# Urukul_FPGA_Config.net
KiCad netlist of a schematic drawn in Altium Designer
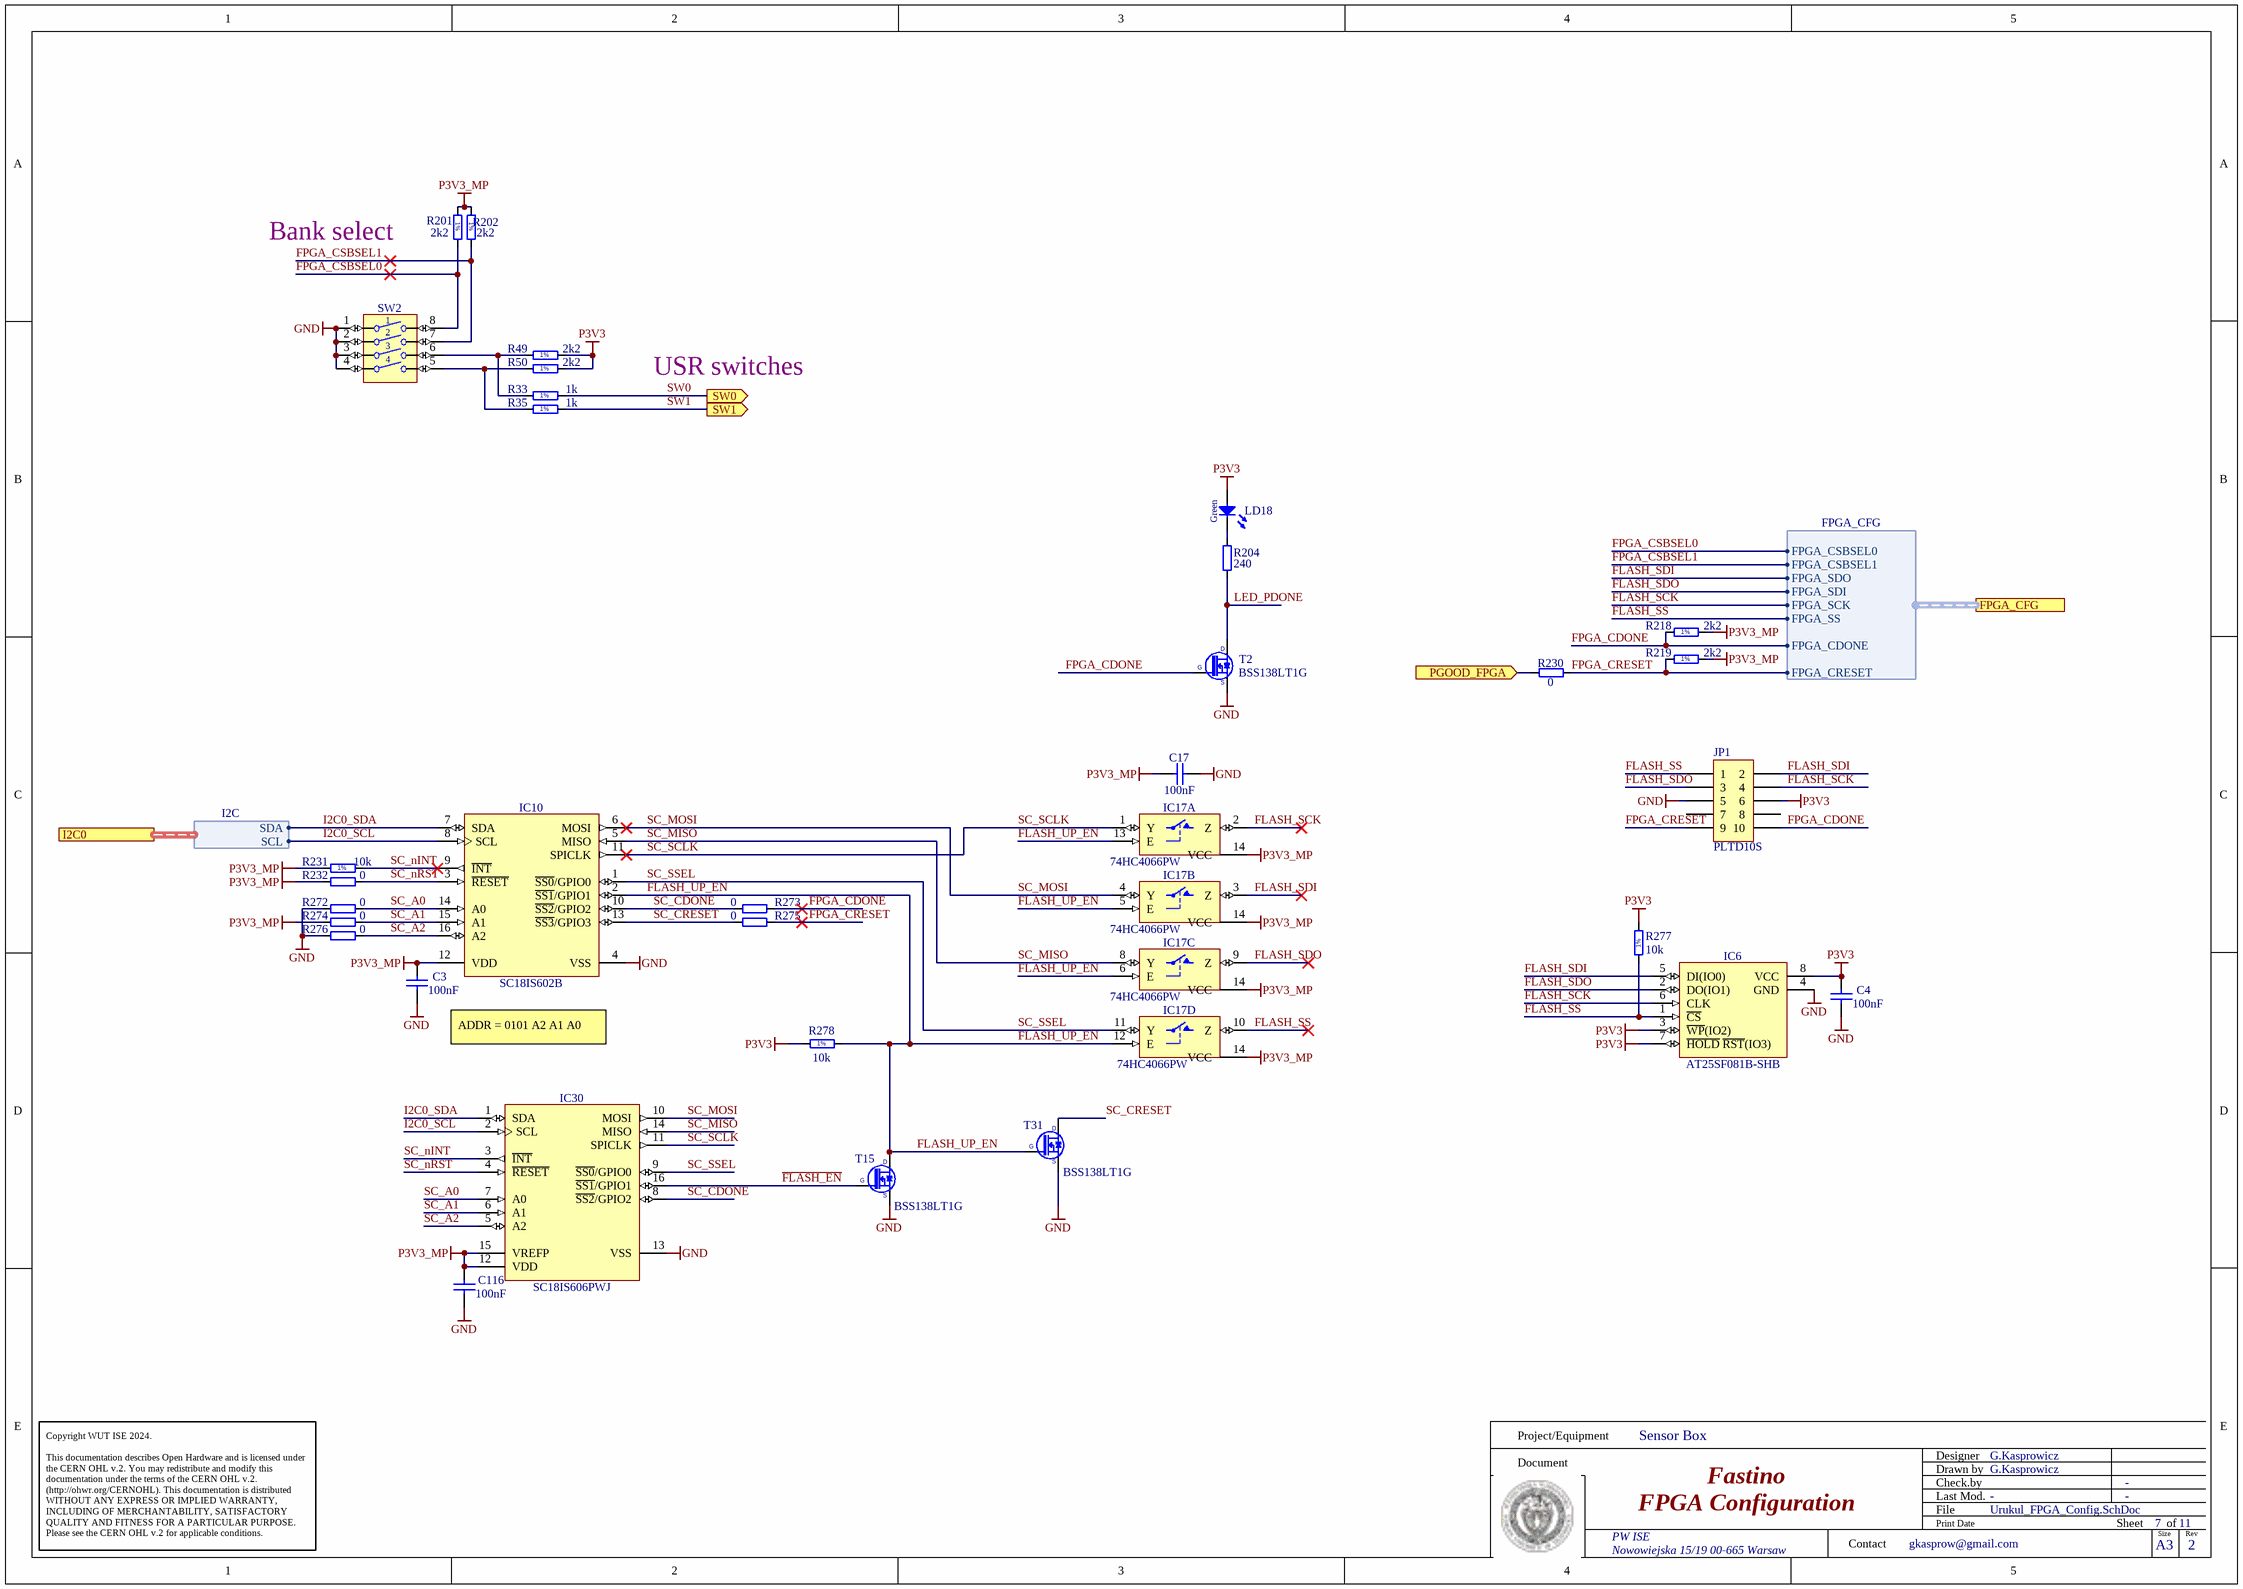
[diagram p0: Urukul_FPGA_Config.SchDoc]

(export (version "E")
  (design (tool "Eeschema 10.0.6"))
  (components
    (comp (ref "C3")
      (value "100nF")
      (footprint "CAPC1005X55N")
      (description "Non-polarised capacitor")
      (fields
        (field (name "PART NUMBER") "CC0402_100NF_16V_10%_X5R")
        (field (name "VOLTAGE") "16V")
        (field (name "AUTHOR") "CERN DEM JLC")
      )
      (libsource (lib "Capacitors") (part "Capacitor - non polarized"))
    )
    (comp (ref "C4")
      (value "100nF")
      (footprint "CAPC1005X55N")
      (description "Non-polarised capacitor")
      (fields
        (field (name "PART NUMBER") "CC0402_100NF_16V_10%_X5R")
        (field (name "VOLTAGE") "16V")
        (field (name "AUTHOR") "CERN DEM JLC")
      )
      (libsource (lib "Capacitors") (part "Capacitor - non polarized"))
    )
    (comp (ref "C17")
      (value "100nF")
      (footprint "CAPC1005X55N")
      (description "Non-polarised capacitor")
      (fields
        (field (name "PART NUMBER") "CC0402_100NF_16V_10%_X5R")
        (field (name "VOLTAGE") "16V")
        (field (name "AUTHOR") "CERN DEM JLC")
      )
      (libsource (lib "Capacitors") (part "Capacitor - non polarized"))
    )
    (comp (ref "C116")
      (value "100nF")
      (footprint "CAPC1005X55N")
      (description "Non-polarised capacitor")
      (fields
        (field (name "PART NUMBER") "CC0402_100NF_16V_10%_X5R")
        (field (name "VOLTAGE") "16V")
        (field (name "AUTHOR") "CERN DEM JLC")
      )
      (libsource (lib "Capacitors") (part "Capacitor - non polarized"))
    )
    (comp (ref "IC6")
      (value "AT25SF081B-SHB")
      (footprint "SOIC127P790X216-8N")
      (description "8M-bit Serial Flash Memory with uniform 4KB sectors and Dual/Quad SPI and QPI")
      (fields (field (name "MANUFACTURER") "Renesas") (field (name "AUTHOR") "GK"))
      (libsource (lib "ICS-logic") (part "MEM_AT25SF081B-SHB"))
    )
    (comp (ref "IC10")
      (value "SC18IS602B")
      (footprint "SOP65P640X110-16N")
      (description "I2C-bus to SPI bridge")
      (fields (field (name "MANUFACTURER") "NXP SEMICONDUCTORS") (field (name "AUTHOR") "CERN DEM MR"))
      (libsource (lib "ICs And Semiconductors") (part "SC18IS602B"))
    )
    (comp (ref "IC17")
      (value "74HC4066PW")
      (footprint "SOP65P640X110-14N")
      (fields (field (name "MANUFACTURER") "NXP SEMICONDUCTORS") (field (name "AUTHOR") "CERN DEM JLC"))
      (libsource (lib "ICs And Semiconductors") (part "4066"))
    )
    (comp (ref "IC30")
      (value "SC18IS606PWJ")
      (footprint "SOP65P640X110-16N")
      (description "I2C-bus to SPI bridge")
      (fields (field (name "MANUFACTURER") "NXP SEMICONDUCTORS") (field (name "AUTHOR") "GK"))
      (libsource (lib "ICS-logic") (part "SC18IS606PWJ"))
    )
    (comp (ref "JP1")
      (value "PLTD10S")
      (footprint "PLTD10S")
      (description "Goldpin 2.54mm, male header")
      (fields (field (name "MANUFACTURER") "Maritex"))
      (libsource (lib "LIBRARY_SCH") (part "CON_2x5 2.54 male SMT"))
    )
    (comp (ref "LD18")
      (value "Green")
      (footprint "LED_AVAGO_HSME-C120")
      (description "LED Green 1C 2A")
      (fields
        (field (name "PART NUMBER") "LED_AVAGO_HSME-C120")
        (field (name "MANUFACTURER") "AVAGO TECHNOLOGIES")
        (field (name "AUTHOR") "CERN DEM JMW")
      )
      (libsource (lib "ICs And Semiconductors") (part "LED Green 1C 2A"))
    )
    (comp (ref "R33")
      (value "1k")
      (footprint "RESC1005X40N")
      (description "Resistor - 1%")
      (fields
        (field (name "PART NUMBER") "R0402_1K_1%_0.0625W_100PPM")
        (field (name "POWER") "0.0625W")
        (field (name "AUTHOR") "CERN DEM JLC")
      )
      (libsource (lib "Resistors") (part "Resistor - 1%"))
    )
    (comp (ref "R35")
      (value "1k")
      (footprint "RESC1005X40N")
      (description "Resistor - 1%")
      (fields
        (field (name "PART NUMBER") "R0402_1K_1%_0.0625W_100PPM")
        (field (name "POWER") "0.0625W")
        (field (name "AUTHOR") "CERN DEM JLC")
      )
      (libsource (lib "Resistors") (part "Resistor - 1%"))
    )
    (comp (ref "R49")
      (value "2k2")
      (footprint "RESC1005X40N")
      (description "Resistor - 1%")
      (fields
        (field (name "PART NUMBER") "R0402_2K2_1%_0.0625W_100PPM")
        (field (name "POWER") "0.0625W")
        (field (name "AUTHOR") "CERN DEM JLC")
      )
      (libsource (lib "Resistors") (part "Resistor - 1%"))
    )
    (comp (ref "R50")
      (value "2k2")
      (footprint "RESC1005X40N")
      (description "Resistor - 1%")
      (fields
        (field (name "PART NUMBER") "R0402_2K2_1%_0.0625W_100PPM")
        (field (name "POWER") "0.0625W")
        (field (name "AUTHOR") "CERN DEM JLC")
      )
      (libsource (lib "Resistors") (part "Resistor - 1%"))
    )
    (comp (ref "R201")
      (value "2k2")
      (footprint "RESC1005X40N")
      (description "Resistor - 1%")
      (fields
        (field (name "PART NUMBER") "R0402_2K2_1%_0.0625W_100PPM")
        (field (name "POWER") "0.0625W")
        (field (name "AUTHOR") "CERN DEM JLC")
      )
      (libsource (lib "Resistors") (part "Resistor - 1%"))
    )
    (comp (ref "R202")
      (value "2k2")
      (footprint "RESC1005X40N")
      (description "Resistor - 1%")
      (fields
        (field (name "PART NUMBER") "R0402_2K2_1%_0.0625W_100PPM")
        (field (name "POWER") "0.0625W")
        (field (name "AUTHOR") "CERN DEM JLC")
      )
      (libsource (lib "Resistors") (part "Resistor - 1%"))
    )
    (comp (ref "R204")
      (value "240")
      (footprint "RESC1005X40N")
      (description "Resistor - 1%")
      (fields
        (field (name "PART NUMBER") "R0402_240R_1%_0.0625W_100PPM")
        (field (name "POWER") "0.0625W")
        (field (name "AUTHOR") "CERN DEM JLC")
      )
      (libsource (lib "Resistors") (part "Resistor - 1%"))
    )
    (comp (ref "R218")
      (value "2k2")
      (footprint "RESC1005X40N")
      (description "Resistor - 1%")
      (fields
        (field (name "PART NUMBER") "R0402_2K2_1%_0.0625W_100PPM")
        (field (name "POWER") "0.0625W")
        (field (name "AUTHOR") "CERN DEM JLC")
      )
      (libsource (lib "Resistors") (part "Resistor - 1%"))
    )
    (comp (ref "R219")
      (value "2k2")
      (footprint "RESC1005X40N")
      (description "Resistor - 1%")
      (fields
        (field (name "PART NUMBER") "R0402_2K2_1%_0.0625W_100PPM")
        (field (name "POWER") "0.0625W")
        (field (name "AUTHOR") "CERN DEM JLC")
      )
      (libsource (lib "Resistors") (part "Resistor - 1%"))
    )
    (comp (ref "R230")
      (value "0")
      (footprint "RESC1005X40N")
      (description "Resistor")
      (fields
        (field (name "PART NUMBER") "R0402_0R_JUMPER")
        (field (name "MANUFACTURER") "GENERIC")
        (field (name "AUTHOR") "CERN DEM JLC")
      )
      (libsource (lib "Resistors") (part "Resistor"))
    )
    (comp (ref "R231")
      (value "10k")
      (footprint "RESC1005X40N")
      (description "Resistor - 1%")
      (fields
        (field (name "PART NUMBER") "R0402_10K_1%_0.0625W_100PPM")
        (field (name "POWER") "0.0625W")
        (field (name "AUTHOR") "CERN DEM JLC")
      )
      (libsource (lib "Resistors") (part "Resistor - 1%"))
    )
    (comp (ref "R232")
      (value "0")
      (footprint "RESC1005X40N")
      (description "Resistor")
      (fields
        (field (name "PART NUMBER") "R0402_0R_JUMPER")
        (field (name "MANUFACTURER") "GENERIC")
        (field (name "AUTHOR") "CERN DEM JLC")
      )
      (libsource (lib "Resistors") (part "Resistor"))
    )
    (comp (ref "R272")
      (value "0")
      (footprint "RESC1005X40N")
      (description "Resistor")
      (fields
        (field (name "PART NUMBER") "R0402_0R_JUMPER")
        (field (name "MANUFACTURER") "GENERIC")
        (field (name "AUTHOR") "CERN DEM JLC")
      )
      (libsource (lib "Resistors") (part "Resistor"))
    )
    (comp (ref "R273")
      (value "0")
      (footprint "RESC1005X40N")
      (description "Resistor")
      (fields
        (field (name "PART NUMBER") "R0402_0R_JUMPER")
        (field (name "MANUFACTURER") "GENERIC")
        (field (name "AUTHOR") "CERN DEM JLC")
      )
      (libsource (lib "Resistors") (part "Resistor"))
    )
    (comp (ref "R274")
      (value "0")
      (footprint "RESC1005X40N")
      (description "Resistor")
      (fields
        (field (name "PART NUMBER") "R0402_0R_JUMPER")
        (field (name "MANUFACTURER") "GENERIC")
        (field (name "AUTHOR") "CERN DEM JLC")
      )
      (libsource (lib "Resistors") (part "Resistor"))
    )
    (comp (ref "R275")
      (value "0")
      (footprint "RESC1005X40N")
      (description "Resistor")
      (fields
        (field (name "PART NUMBER") "R0402_0R_JUMPER")
        (field (name "MANUFACTURER") "GENERIC")
        (field (name "AUTHOR") "CERN DEM JLC")
      )
      (libsource (lib "Resistors") (part "Resistor"))
    )
    (comp (ref "R276")
      (value "0")
      (footprint "RESC1005X40N")
      (description "Resistor")
      (fields
        (field (name "PART NUMBER") "R0402_0R_JUMPER")
        (field (name "MANUFACTURER") "GENERIC")
        (field (name "AUTHOR") "CERN DEM JLC")
      )
      (libsource (lib "Resistors") (part "Resistor"))
    )
    (comp (ref "R277")
      (value "10k")
      (footprint "RESC1005X40N")
      (description "Resistor - 1%")
      (fields
        (field (name "PART NUMBER") "R0402_10K_1%_0.0625W_100PPM")
        (field (name "POWER") "0.0625W")
        (field (name "AUTHOR") "CERN DEM JLC")
      )
      (libsource (lib "Resistors") (part "Resistor - 1%"))
    )
    (comp (ref "R278")
      (value "10k")
      (footprint "RESC1005X40N")
      (description "Resistor - 1%")
      (fields
        (field (name "PART NUMBER") "R0402_10K_1%_0.0625W_100PPM")
        (field (name "POWER") "0.0625W")
        (field (name "AUTHOR") "CERN DEM JLC")
      )
      (libsource (lib "Resistors") (part "Resistor - 1%"))
    )
    (comp (ref "SW2")
      (value "Switch")
      (footprint "SW_TYCO_1571983-4")
      (description "4 Ways SPST DIP Switch")
      (fields
        (field (name "PART NUMBER") "SW_TYCO_1571983-4")
        (field (name "MANUFACTURER") "TYCO")
        (field (name "AUTHOR") "CERN DEM JLC")
      )
      (libsource (lib "Eletro-mechanical") (part "SW 4x SPST DIP Switch"))
    )
    (comp (ref "T2")
      (value "BSS138LT1G")
      (footprint "SOT95P240X110-3N")
      (description "N-CHANNEL MOSFET WITH DIODE")
      (fields (field (name "MANUFACTURER") "ON SEMICONDUCTOR") (field (name "AUTHOR") "CERN DEM JLC"))
      (libsource (lib "ICs And Semiconductors") (part "N-MOSFET-D 1G 2S 3D"))
    )
    (comp (ref "T15")
      (value "BSS138LT1G")
      (footprint "SOT95P240X110-3N")
      (description "N-CHANNEL MOSFET WITH DIODE")
      (fields (field (name "MANUFACTURER") "ON SEMICONDUCTOR") (field (name "AUTHOR") "CERN DEM JLC"))
      (libsource (lib "ICs And Semiconductors") (part "N-MOSFET-D 1G 2S 3D"))
    )
    (comp (ref "T31")
      (value "BSS138LT1G")
      (footprint "SOT95P240X110-3N")
      (description "N-CHANNEL MOSFET WITH DIODE")
      (fields (field (name "MANUFACTURER") "ON SEMICONDUCTOR") (field (name "AUTHOR") "CERN DEM JLC"))
      (libsource (lib "ICs And Semiconductors") (part "N-MOSFET-D 1G 2S 3D"))
    )
  )
  (nets
    (net (code "3") (name "/FLASH_SCK") (class "Default")
      (node (ref "IC17") (pin "2") (pinfunction "Z_2") (pintype "bidirectional"))
      (node (ref "IC6") (pin "6") (pinfunction "CLK_6") (pintype "input"))
      (node (ref "JP1") (pin "4") (pinfunction "4_4") (pintype "passive"))
    )
    (net (code "4") (name "/FLASH_SDI") (class "Default")
      (node (ref "IC17") (pin "3") (pinfunction "Z_3") (pintype "bidirectional"))
      (node (ref "IC6") (pin "5") (pinfunction "DI(IO0)_5") (pintype "bidirectional"))
      (node (ref "JP1") (pin "2") (pinfunction "2_2") (pintype "passive"))
    )
    (net (code "5") (name "/FLASH_SDO") (class "Default")
      (node (ref "IC17") (pin "9") (pinfunction "Z_9") (pintype "bidirectional"))
      (node (ref "IC6") (pin "2") (pinfunction "DO(IO1)_2") (pintype "bidirectional"))
      (node (ref "JP1") (pin "3") (pinfunction "3_3") (pintype "passive"))
    )
    (net (code "6") (name "/FLASH_SS") (class "Default")
      (node (ref "IC17") (pin "10") (pinfunction "Z_10") (pintype "bidirectional"))
      (node (ref "IC6") (pin "1") (pinfunction "~{CS}_1") (pintype "input"))
      (node (ref "JP1") (pin "1") (pinfunction "1_1") (pintype "passive"))
      (node (ref "R277") (pin "1") (pinfunction "1_1") (pintype "passive"))
    )
    (net (code "7") (name "/FLASH_UP_EN") (class "Default")
      (node (ref "IC10") (pin "2") (pinfunction "~{SS1}/GPIO1_2") (pintype "bidirectional"))
      (node (ref "IC17") (pin "12") (pinfunction "E_12") (pintype "input"))
      (node (ref "IC17") (pin "13") (pinfunction "E_13") (pintype "input"))
      (node (ref "IC17") (pin "5") (pinfunction "E_5") (pintype "input"))
      (node (ref "IC17") (pin "6") (pinfunction "E_6") (pintype "input"))
      (node (ref "R278") (pin "2") (pinfunction "2_2") (pintype "passive"))
      (node (ref "T15") (pin "3") (pinfunction "D_3") (pintype "passive"))
      (node (ref "T31") (pin "1") (pinfunction "G_1") (pintype "passive"))
    )
    (net (code "8") (name "/FPGA_CDONE") (class "Default")
      (node (ref "JP1") (pin "10") (pinfunction "10_10") (pintype "passive"))
      (node (ref "R218") (pin "1") (pinfunction "1_1") (pintype "passive"))
      (node (ref "R273") (pin "1") (pinfunction "1_1") (pintype "passive"))
      (node (ref "T2") (pin "1") (pinfunction "G_1") (pintype "passive"))
    )
    (net (code "9") (name "/FPGA_CRESET") (class "Default")
      (node (ref "JP1") (pin "9") (pinfunction "9_9") (pintype "passive"))
      (node (ref "R219") (pin "1") (pinfunction "1_1") (pintype "passive"))
      (node (ref "R230") (pin "2") (pinfunction "2_2") (pintype "passive"))
      (node (ref "R275") (pin "1") (pinfunction "1_1") (pintype "passive"))
    )
    (net (code "10") (name "/FPGA_CSBSEL0") (class "Default")
      (node (ref "R201") (pin "2") (pinfunction "2_2") (pintype "passive"))
      (node (ref "SW2") (pin "8") (pinfunction "8_8") (pintype "bidirectional"))
    )
    (net (code "11") (name "/FPGA_CSBSEL1") (class "Default")
      (node (ref "R202") (pin "2") (pinfunction "2_2") (pintype "passive"))
      (node (ref "SW2") (pin "7") (pinfunction "7_7") (pintype "bidirectional"))
    )
    (net (code "12") (name "/I2C0_SCL") (class "Default")
      (node (ref "IC10") (pin "8") (pinfunction "SCL_8") (pintype "input"))
      (node (ref "IC30") (pin "2") (pinfunction "SCL_2") (pintype "input"))
    )
    (net (code "13") (name "/I2C0_SDA") (class "Default")
      (node (ref "IC10") (pin "7") (pinfunction "SDA_7") (pintype "bidirectional"))
      (node (ref "IC30") (pin "1") (pinfunction "SDA_1") (pintype "bidirectional"))
    )
    (net (code "14") (name "/LED_PDONE") (class "Default")
      (node (ref "R204") (pin "1") (pinfunction "1_1") (pintype "passive"))
      (node (ref "T2") (pin "3") (pinfunction "D_3") (pintype "passive"))
    )
    (net (code "15") (name "/PGOOD_FPGA") (class "Default")
      (node (ref "R230") (pin "1") (pinfunction "1_1") (pintype "passive"))
    )
    (net (code "16") (name "/SC_A0") (class "Default")
      (node (ref "IC10") (pin "14") (pinfunction "A0_14") (pintype "input"))
      (node (ref "IC30") (pin "7") (pinfunction "A0_7") (pintype "input"))
      (node (ref "R272") (pin "1") (pinfunction "1_1") (pintype "passive"))
    )
    (net (code "17") (name "/SC_A1") (class "Default")
      (node (ref "IC10") (pin "15") (pinfunction "A1_15") (pintype "input"))
      (node (ref "IC30") (pin "6") (pinfunction "A1_6") (pintype "input"))
      (node (ref "R274") (pin "1") (pinfunction "1_1") (pintype "passive"))
    )
    (net (code "18") (name "/SC_A2") (class "Default")
      (node (ref "IC10") (pin "16") (pinfunction "A2_16") (pintype "bidirectional"))
      (node (ref "IC30") (pin "5") (pinfunction "A2_5") (pintype "bidirectional"))
      (node (ref "R276") (pin "1") (pinfunction "1_1") (pintype "passive"))
    )
    (net (code "19") (name "/SC_CDONE") (class "Default")
      (node (ref "IC10") (pin "10") (pinfunction "~{SS2}/GPIO2_10") (pintype "bidirectional"))
      (node (ref "IC30") (pin "8") (pinfunction "~{SS2}/GPIO2_8") (pintype "bidirectional"))
      (node (ref "R273") (pin "2") (pinfunction "2_2") (pintype "passive"))
    )
    (net (code "20") (name "/SC_CRESET") (class "Default")
      (node (ref "IC10") (pin "13") (pinfunction "~{SS3}/GPIO3_13") (pintype "bidirectional"))
      (node (ref "R275") (pin "2") (pinfunction "2_2") (pintype "passive"))
      (node (ref "T31") (pin "3") (pinfunction "D_3") (pintype "passive"))
    )
    (net (code "21") (name "/SC_MISO") (class "Default")
      (node (ref "IC10") (pin "5") (pinfunction "MISO_5") (pintype "input"))
      (node (ref "IC17") (pin "8") (pinfunction "Y_8") (pintype "bidirectional"))
      (node (ref "IC30") (pin "14") (pinfunction "MISO_14") (pintype "input"))
    )
    (net (code "22") (name "/SC_MOSI") (class "Default")
      (node (ref "IC10") (pin "6") (pinfunction "MOSI_6") (pintype "output"))
      (node (ref "IC17") (pin "4") (pinfunction "Y_4") (pintype "bidirectional"))
      (node (ref "IC30") (pin "10") (pinfunction "MOSI_10") (pintype "output"))
    )
    (net (code "23") (name "/SC_SCLK") (class "Default")
      (node (ref "IC10") (pin "11") (pinfunction "SPICLK_11") (pintype "output"))
      (node (ref "IC17") (pin "1") (pinfunction "Y_1") (pintype "bidirectional"))
      (node (ref "IC30") (pin "11") (pinfunction "SPICLK_11") (pintype "output"))
    )
    (net (code "24") (name "/SC_SSEL") (class "Default")
      (node (ref "IC10") (pin "1") (pinfunction "~{SS0}/GPIO0_1") (pintype "bidirectional"))
      (node (ref "IC17") (pin "11") (pinfunction "Y_11") (pintype "bidirectional"))
      (node (ref "IC30") (pin "9") (pinfunction "~{SS0}/GPIO0_9") (pintype "bidirectional"))
    )
    (net (code "25") (name "/SC_nINT") (class "Default")
      (node (ref "IC10") (pin "9") (pinfunction "~{INT}_9") (pintype "output"))
      (node (ref "IC30") (pin "3") (pinfunction "~{INT}_3") (pintype "output"))
      (node (ref "R231") (pin "2") (pinfunction "2_2") (pintype "passive"))
    )
    (net (code "26") (name "/SC_nRST") (class "Default")
      (node (ref "IC10") (pin "3") (pinfunction "~{RESET}_3") (pintype "input"))
      (node (ref "IC30") (pin "4") (pinfunction "~{RESET}_4") (pintype "input"))
      (node (ref "R232") (pin "1") (pinfunction "1_1") (pintype "passive"))
    )
    (net (code "27") (name "/SW0") (class "Default")
      (node (ref "R33") (pin "2") (pinfunction "2_2") (pintype "passive"))
    )
    (net (code "28") (name "/SW1") (class "Default")
      (node (ref "R35") (pin "2") (pinfunction "2_2") (pintype "passive"))
    )
    (net (code "31") (name "/~{FLASH_EN}") (class "Default")
      (node (ref "IC30") (pin "16") (pinfunction "~{SS1}/GPIO1_16") (pintype "bidirectional"))
      (node (ref "T15") (pin "1") (pinfunction "G_1") (pintype "passive"))
    )
    (net (code "32") (name "GND") (class "Default")
      (node (ref "C116") (pin "1") (pinfunction "1_1") (pintype "passive"))
      (node (ref "C17") (pin "2") (pinfunction "2_2") (pintype "passive"))
      (node (ref "C3") (pin "1") (pinfunction "1_1") (pintype "passive"))
      (node (ref "C4") (pin "1") (pinfunction "1_1") (pintype "passive"))
      (node (ref "IC10") (pin "4") (pinfunction "VSS_4") (pintype "power_in"))
      (node (ref "IC17") (pin "7") (pinfunction "GND_7") (pintype "power_in"))
      (node (ref "IC30") (pin "13") (pinfunction "VSS_13") (pintype "power_in"))
      (node (ref "IC6") (pin "4") (pinfunction "GND_4") (pintype "power_in"))
      (node (ref "JP1") (pin "5") (pinfunction "5_5") (pintype "passive"))
      (node (ref "R272") (pin "2") (pinfunction "2_2") (pintype "passive"))
      (node (ref "R276") (pin "2") (pinfunction "2_2") (pintype "passive"))
      (node (ref "SW2") (pin "1") (pinfunction "1_1") (pintype "bidirectional"))
      (node (ref "SW2") (pin "2") (pinfunction "2_2") (pintype "bidirectional"))
      (node (ref "SW2") (pin "3") (pinfunction "3_3") (pintype "bidirectional"))
      (node (ref "SW2") (pin "4") (pinfunction "4_4") (pintype "bidirectional"))
      (node (ref "T15") (pin "2") (pinfunction "S_2") (pintype "passive"))
      (node (ref "T2") (pin "2") (pinfunction "S_2") (pintype "passive"))
      (node (ref "T31") (pin "2") (pinfunction "S_2") (pintype "passive"))
    )
    (net (code "33") (name "Net-(LD18-C)") (class "Default")
      (node (ref "LD18") (pin "1") (pinfunction "C_1") (pintype "passive"))
      (node (ref "R204") (pin "2") (pinfunction "2_2") (pintype "passive"))
    )
    (net (code "34") (name "Net-(R33-Pad1)") (class "Default")
      (node (ref "R33") (pin "1") (pinfunction "1_1") (pintype "passive"))
      (node (ref "R49") (pin "1") (pinfunction "1_1") (pintype "passive"))
      (node (ref "SW2") (pin "6") (pinfunction "6_6") (pintype "bidirectional"))
    )
    (net (code "35") (name "Net-(R35-Pad1)") (class "Default")
      (node (ref "R35") (pin "1") (pinfunction "1_1") (pintype "passive"))
      (node (ref "R50") (pin "1") (pinfunction "1_1") (pintype "passive"))
      (node (ref "SW2") (pin "5") (pinfunction "5_5") (pintype "bidirectional"))
    )
    (net (code "36") (name "P3V3") (class "Default")
      (node (ref "C4") (pin "2") (pinfunction "2_2") (pintype "passive"))
      (node (ref "IC6") (pin "3") (pinfunction "~{WP}(IO2)_3") (pintype "bidirectional"))
      (node (ref "IC6") (pin "7") (pinfunction "~{HOLD}_~{RST}(IO3)_7") (pintype "bidirectional"))
      (node (ref "IC6") (pin "8") (pinfunction "VCC_8") (pintype "power_in"))
      (node (ref "JP1") (pin "6") (pinfunction "6_6") (pintype "passive"))
      (node (ref "LD18") (pin "2") (pinfunction "A_2") (pintype "passive"))
      (node (ref "R277") (pin "2") (pinfunction "2_2") (pintype "passive"))
      (node (ref "R278") (pin "1") (pinfunction "1_1") (pintype "passive"))
      (node (ref "R49") (pin "2") (pinfunction "2_2") (pintype "passive"))
      (node (ref "R50") (pin "2") (pinfunction "2_2") (pintype "passive"))
    )
    (net (code "37") (name "P3V3_MP") (class "Default")
      (node (ref "C116") (pin "2") (pinfunction "2_2") (pintype "passive"))
      (node (ref "C17") (pin "1") (pinfunction "1_1") (pintype "passive"))
      (node (ref "C3") (pin "2") (pinfunction "2_2") (pintype "passive"))
      (node (ref "IC10") (pin "12") (pinfunction "VDD_12") (pintype "power_in"))
      (node (ref "IC17") (pin "14") (pinfunction "VCC_14") (pintype "power_in"))
      (node (ref "IC30") (pin "12") (pinfunction "VDD_12") (pintype "power_in"))
      (node (ref "IC30") (pin "15") (pinfunction "VREFP_15") (pintype "power_in"))
      (node (ref "R201") (pin "1") (pinfunction "1_1") (pintype "passive"))
      (node (ref "R202") (pin "1") (pinfunction "1_1") (pintype "passive"))
      (node (ref "R218") (pin "2") (pinfunction "2_2") (pintype "passive"))
      (node (ref "R219") (pin "2") (pinfunction "2_2") (pintype "passive"))
      (node (ref "R231") (pin "1") (pinfunction "1_1") (pintype "passive"))
      (node (ref "R232") (pin "2") (pinfunction "2_2") (pintype "passive"))
      (node (ref "R274") (pin "2") (pinfunction "2_2") (pintype "passive"))
    )
    (net (code "38") (name "unconnected-(JP1-Pad7)") (class "Default")
      (node (ref "JP1") (pin "7") (pinfunction "7_7") (pintype "passive"))
    )
    (net (code "39") (name "unconnected-(JP1-Pad8)") (class "Default")
      (node (ref "JP1") (pin "8") (pinfunction "8_8") (pintype "passive"))
    )
  )
)
